# S7CAS-PLEIADES-CARTE-MERE_P02_CONNECTORS.net
KiCad netlist of a schematic drawn in Altium Designer
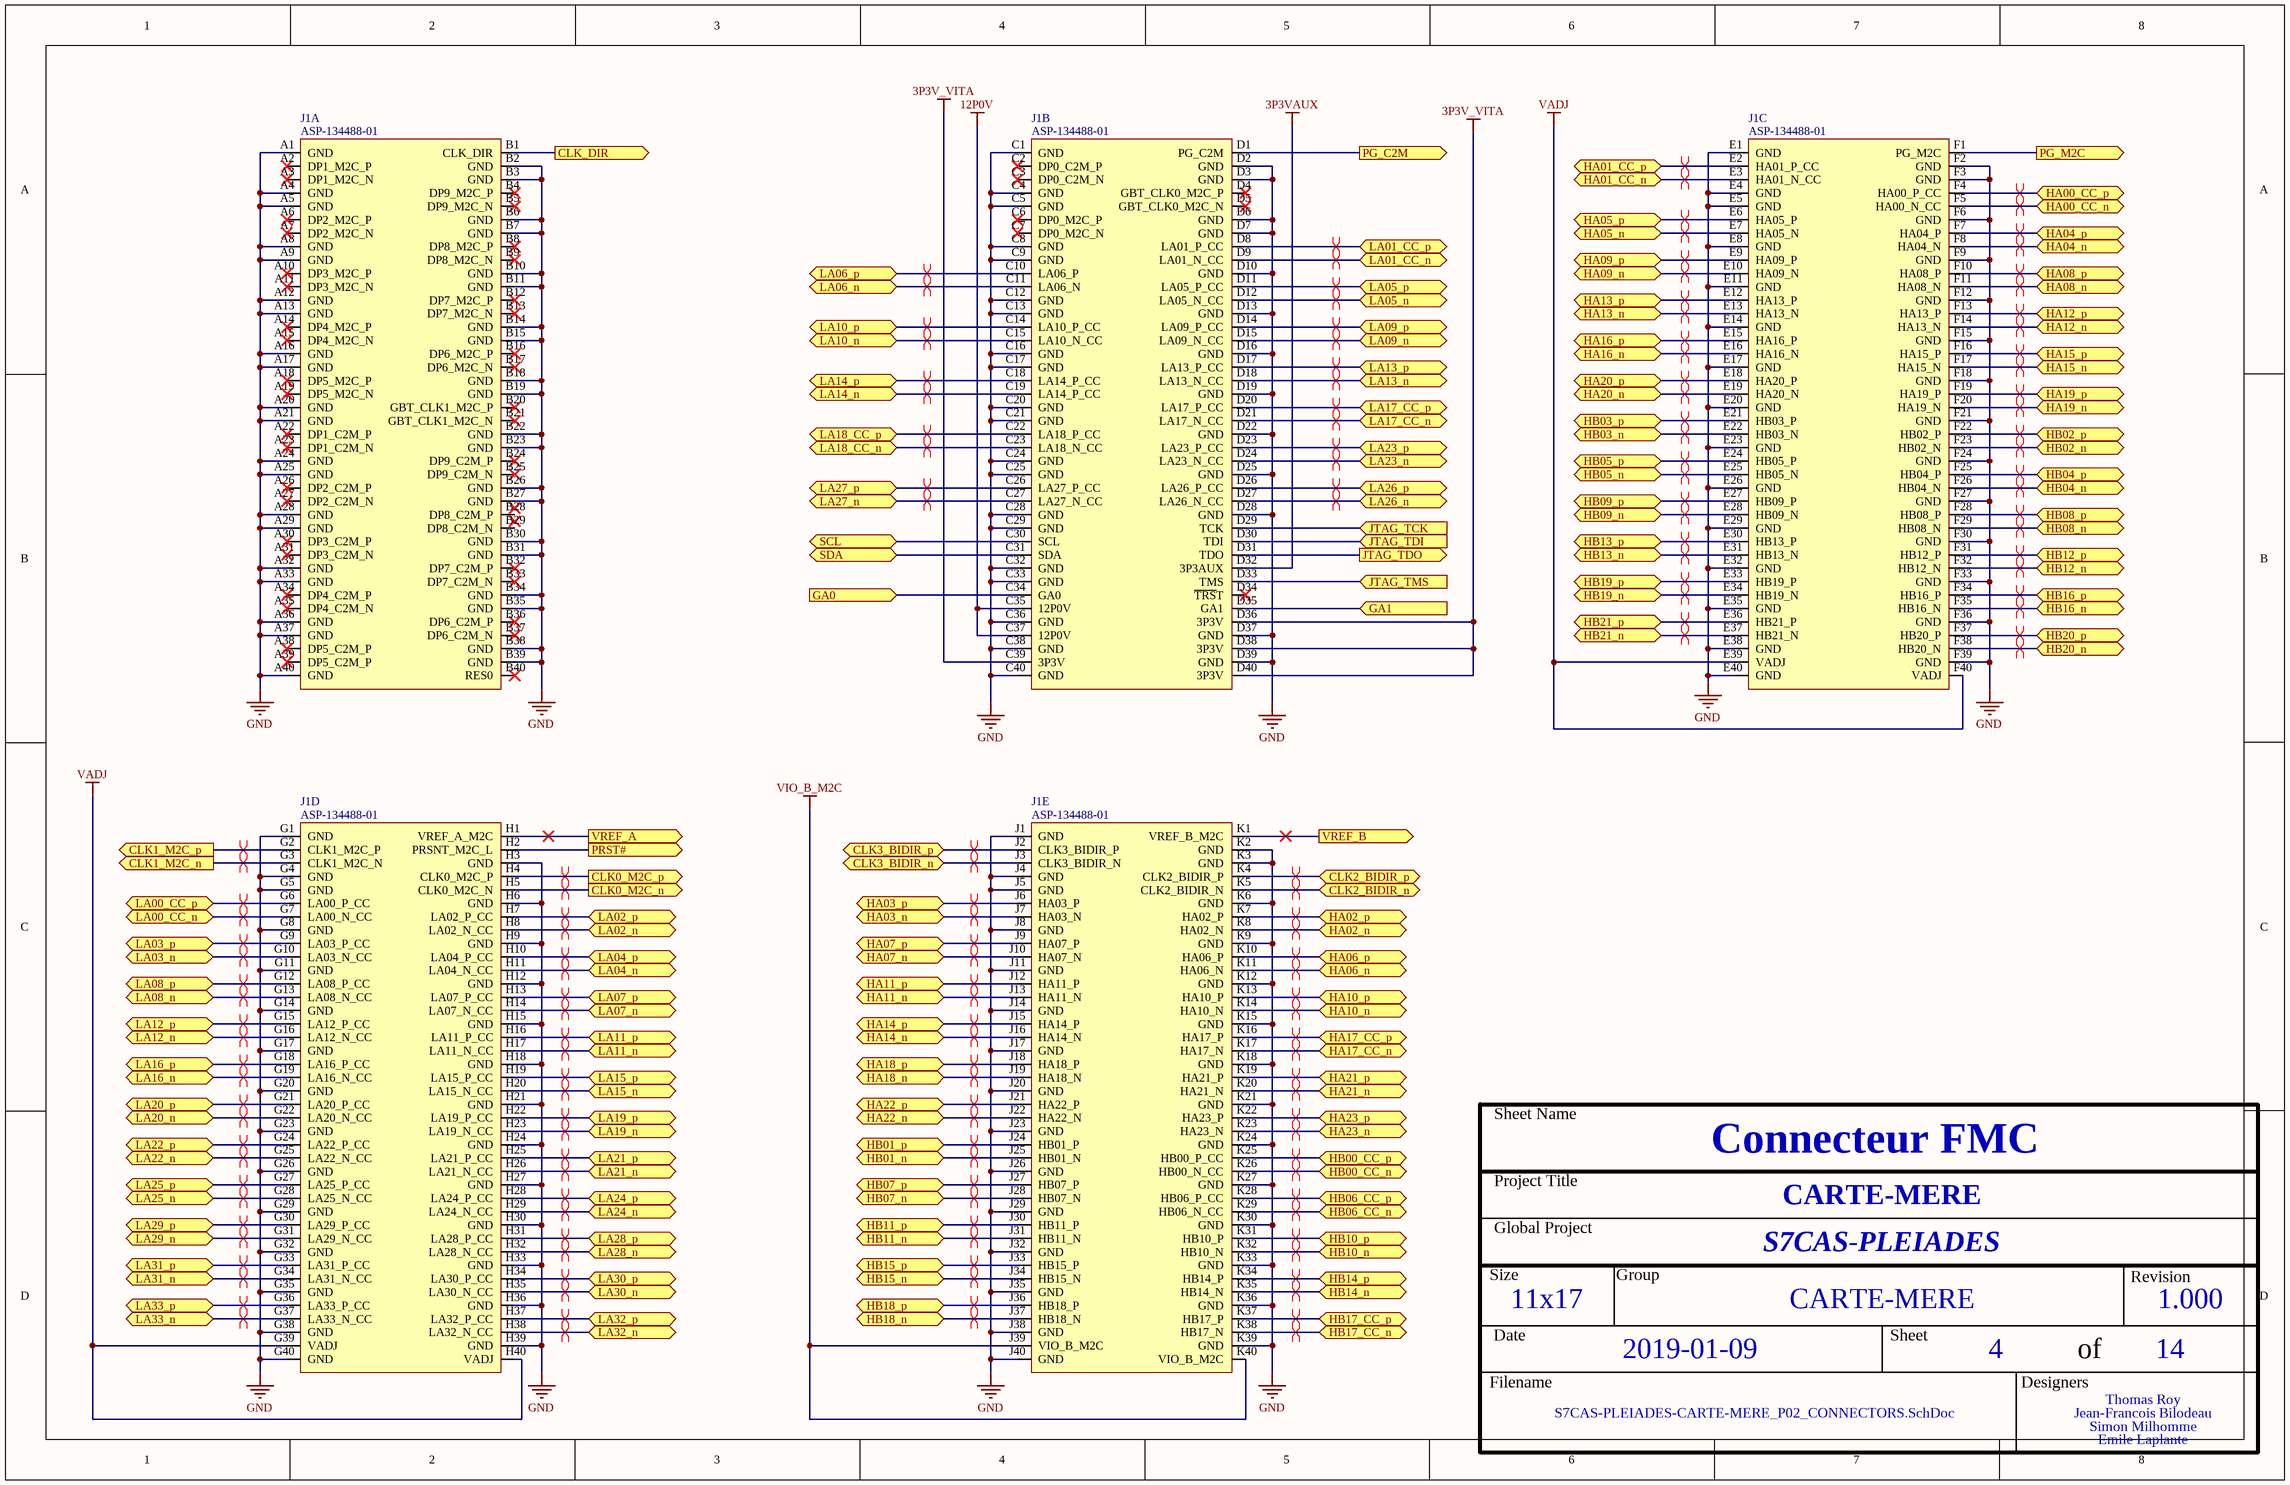
[diagram p0: S7CAS-PLEIADES-CARTE-MERE_P02_CONNECTORS.SchDoc]

(export (version "E")
  (design (tool "Eeschema 10.0.6"))
  (components
    (comp (ref "J1")
      (value "ASP-134488-01")
      (footprint "CONN_SAMTEC_ASP-134488-01")
      (description "CONN - VITA 57 MEZZ MALE (DAUGHTERBOARD) HIGH DENSITY - SMD-400")
      (fields
        (field (name "VOLTAGE") "240VAC")
        (field (name "MFG") "Samtec")
        (field (name "CREATEDBY") "Jonathan Bouchard")
      )
      (libsource (lib "S7CAS_Lib2019_REV1_00") (part "CONN_SAMTEC_ASP-134488-01"))
    )
  )
  (nets
    (net (code "1") (name "/CLK0_M2C_n") (class "Default")
      (node (ref "J1") (pin "H5") (pinfunction "CLK0_M2C_N_H5") (pintype "passive"))
    )
    (net (code "2") (name "/CLK0_M2C_p") (class "Default")
      (node (ref "J1") (pin "H4") (pinfunction "CLK0_M2C_P_H4") (pintype "passive"))
    )
    (net (code "3") (name "/CLK1_M2C_n") (class "Default")
      (node (ref "J1") (pin "G3") (pinfunction "CLK1_M2C_N_G3") (pintype "passive"))
    )
    (net (code "4") (name "/CLK1_M2C_p") (class "Default")
      (node (ref "J1") (pin "G2") (pinfunction "CLK1_M2C_P_G2") (pintype "passive"))
    )
    (net (code "5") (name "/CLK2_BIDIR_n") (class "Default")
      (node (ref "J1") (pin "K5") (pinfunction "CLK2_BIDIR_N_K5") (pintype "passive"))
    )
    (net (code "6") (name "/CLK2_BIDIR_p") (class "Default")
      (node (ref "J1") (pin "K4") (pinfunction "CLK2_BIDIR_P_K4") (pintype "passive"))
    )
    (net (code "7") (name "/CLK3_BIDIR_n") (class "Default")
      (node (ref "J1") (pin "J3") (pinfunction "CLK3_BIDIR_N_J3") (pintype "passive"))
    )
    (net (code "8") (name "/CLK3_BIDIR_p") (class "Default")
      (node (ref "J1") (pin "J2") (pinfunction "CLK3_BIDIR_P_J2") (pintype "passive"))
    )
    (net (code "9") (name "/CLK_DIR") (class "Default")
      (node (ref "J1") (pin "B1") (pinfunction "CLK_DIR_B1") (pintype "passive"))
    )
    (net (code "10") (name "/GA0") (class "Default")
      (node (ref "J1") (pin "C34") (pinfunction "GA0_C34") (pintype "passive"))
    )
    (net (code "11") (name "/GA1") (class "Default")
      (node (ref "J1") (pin "D35") (pinfunction "GA1_D35") (pintype "passive"))
    )
    (net (code "12") (name "/HA00_CC_n") (class "Default")
      (node (ref "J1") (pin "F5") (pinfunction "HA00_N_CC_F5") (pintype "passive"))
    )
    (net (code "13") (name "/HA00_CC_p") (class "Default")
      (node (ref "J1") (pin "F4") (pinfunction "HA00_P_CC_F4") (pintype "passive"))
    )
    (net (code "14") (name "/HA01_CC_n") (class "Default")
      (node (ref "J1") (pin "E3") (pinfunction "HA01_N_CC_E3") (pintype "passive"))
    )
    (net (code "15") (name "/HA01_CC_p") (class "Default")
      (node (ref "J1") (pin "E2") (pinfunction "HA01_P_CC_E2") (pintype "passive"))
    )
    (net (code "16") (name "/HA02_n") (class "Default")
      (node (ref "J1") (pin "K8") (pinfunction "HA02_N_K8") (pintype "passive"))
    )
    (net (code "17") (name "/HA02_p") (class "Default")
      (node (ref "J1") (pin "K7") (pinfunction "HA02_P_K7") (pintype "passive"))
    )
    (net (code "18") (name "/HA03_n") (class "Default")
      (node (ref "J1") (pin "J7") (pinfunction "HA03_N_J7") (pintype "passive"))
    )
    (net (code "19") (name "/HA03_p") (class "Default")
      (node (ref "J1") (pin "J6") (pinfunction "HA03_P_J6") (pintype "passive"))
    )
    (net (code "20") (name "/HA04_n") (class "Default")
      (node (ref "J1") (pin "F8") (pinfunction "HA04_N_F8") (pintype "passive"))
    )
    (net (code "21") (name "/HA04_p") (class "Default")
      (node (ref "J1") (pin "F7") (pinfunction "HA04_P_F7") (pintype "passive"))
    )
    (net (code "22") (name "/HA05_n") (class "Default")
      (node (ref "J1") (pin "E7") (pinfunction "HA05_N_E7") (pintype "passive"))
    )
    (net (code "23") (name "/HA05_p") (class "Default")
      (node (ref "J1") (pin "E6") (pinfunction "HA05_P_E6") (pintype "passive"))
    )
    (net (code "24") (name "/HA06_n") (class "Default")
      (node (ref "J1") (pin "K11") (pinfunction "HA06_N_K11") (pintype "passive"))
    )
    (net (code "25") (name "/HA06_p") (class "Default")
      (node (ref "J1") (pin "K10") (pinfunction "HA06_P_K10") (pintype "passive"))
    )
    (net (code "26") (name "/HA07_n") (class "Default")
      (node (ref "J1") (pin "J10") (pinfunction "HA07_N_J10") (pintype "passive"))
    )
    (net (code "27") (name "/HA07_p") (class "Default")
      (node (ref "J1") (pin "J9") (pinfunction "HA07_P_J9") (pintype "passive"))
    )
    (net (code "28") (name "/HA08_n") (class "Default")
      (node (ref "J1") (pin "F11") (pinfunction "HA08_N_F11") (pintype "passive"))
    )
    (net (code "29") (name "/HA08_p") (class "Default")
      (node (ref "J1") (pin "F10") (pinfunction "HA08_P_F10") (pintype "passive"))
    )
    (net (code "30") (name "/HA09_n") (class "Default")
      (node (ref "J1") (pin "E10") (pinfunction "HA09_N_E10") (pintype "passive"))
    )
    (net (code "31") (name "/HA09_p") (class "Default")
      (node (ref "J1") (pin "E9") (pinfunction "HA09_P_E9") (pintype "passive"))
    )
    (net (code "32") (name "/HA10_n") (class "Default")
      (node (ref "J1") (pin "K14") (pinfunction "HA10_N_K14") (pintype "passive"))
    )
    (net (code "33") (name "/HA10_p") (class "Default")
      (node (ref "J1") (pin "K13") (pinfunction "HA10_P_K13") (pintype "passive"))
    )
    (net (code "34") (name "/HA11_n") (class "Default")
      (node (ref "J1") (pin "J13") (pinfunction "HA11_N_J13") (pintype "passive"))
    )
    (net (code "35") (name "/HA11_p") (class "Default")
      (node (ref "J1") (pin "J12") (pinfunction "HA11_P_J12") (pintype "passive"))
    )
    (net (code "36") (name "/HA12_n") (class "Default")
      (node (ref "J1") (pin "F14") (pinfunction "HA13_N_F14") (pintype "passive"))
    )
    (net (code "37") (name "/HA12_p") (class "Default")
      (node (ref "J1") (pin "F13") (pinfunction "HA13_P_F13") (pintype "passive"))
    )
    (net (code "38") (name "/HA13_n") (class "Default")
      (node (ref "J1") (pin "E13") (pinfunction "HA13_N_E13") (pintype "passive"))
    )
    (net (code "39") (name "/HA13_p") (class "Default")
      (node (ref "J1") (pin "E12") (pinfunction "HA13_P_E12") (pintype "passive"))
    )
    (net (code "40") (name "/HA14_n") (class "Default")
      (node (ref "J1") (pin "J16") (pinfunction "HA14_N_J16") (pintype "passive"))
    )
    (net (code "41") (name "/HA14_p") (class "Default")
      (node (ref "J1") (pin "J15") (pinfunction "HA14_P_J15") (pintype "passive"))
    )
    (net (code "42") (name "/HA15_n") (class "Default")
      (node (ref "J1") (pin "F17") (pinfunction "HA15_N_F17") (pintype "passive"))
    )
    (net (code "43") (name "/HA15_p") (class "Default")
      (node (ref "J1") (pin "F16") (pinfunction "HA15_P_F16") (pintype "passive"))
    )
    (net (code "44") (name "/HA16_n") (class "Default")
      (node (ref "J1") (pin "E16") (pinfunction "HA16_N_E16") (pintype "passive"))
    )
    (net (code "45") (name "/HA16_p") (class "Default")
      (node (ref "J1") (pin "E15") (pinfunction "HA16_P_E15") (pintype "passive"))
    )
    (net (code "46") (name "/HA17_CC_n") (class "Default")
      (node (ref "J1") (pin "K17") (pinfunction "HA17_N_K17") (pintype "passive"))
    )
    (net (code "47") (name "/HA17_CC_p") (class "Default")
      (node (ref "J1") (pin "K16") (pinfunction "HA17_P_K16") (pintype "passive"))
    )
    (net (code "48") (name "/HA18_n") (class "Default")
      (node (ref "J1") (pin "J19") (pinfunction "HA18_N_J19") (pintype "passive"))
    )
    (net (code "49") (name "/HA18_p") (class "Default")
      (node (ref "J1") (pin "J18") (pinfunction "HA18_P_J18") (pintype "passive"))
    )
    (net (code "50") (name "/HA19_n") (class "Default")
      (node (ref "J1") (pin "F20") (pinfunction "HA19_N_F20") (pintype "passive"))
    )
    (net (code "51") (name "/HA19_p") (class "Default")
      (node (ref "J1") (pin "F19") (pinfunction "HA19_P_F19") (pintype "passive"))
    )
    (net (code "52") (name "/HA20_n") (class "Default")
      (node (ref "J1") (pin "E19") (pinfunction "HA20_N_E19") (pintype "passive"))
    )
    (net (code "53") (name "/HA20_p") (class "Default")
      (node (ref "J1") (pin "E18") (pinfunction "HA20_P_E18") (pintype "passive"))
    )
    (net (code "54") (name "/HA21_n") (class "Default")
      (node (ref "J1") (pin "K20") (pinfunction "HA21_N_K20") (pintype "passive"))
    )
    (net (code "55") (name "/HA21_p") (class "Default")
      (node (ref "J1") (pin "K19") (pinfunction "HA21_P_K19") (pintype "passive"))
    )
    (net (code "56") (name "/HA22_n") (class "Default")
      (node (ref "J1") (pin "J22") (pinfunction "HA22_N_J22") (pintype "passive"))
    )
    (net (code "57") (name "/HA22_p") (class "Default")
      (node (ref "J1") (pin "J21") (pinfunction "HA22_P_J21") (pintype "passive"))
    )
    (net (code "58") (name "/HA23_n") (class "Default")
      (node (ref "J1") (pin "K23") (pinfunction "HA23_N_K23") (pintype "passive"))
    )
    (net (code "59") (name "/HA23_p") (class "Default")
      (node (ref "J1") (pin "K22") (pinfunction "HA23_P_K22") (pintype "passive"))
    )
    (net (code "60") (name "/HB00_CC_n") (class "Default")
      (node (ref "J1") (pin "K26") (pinfunction "HB00_N_CC_K26") (pintype "passive"))
    )
    (net (code "61") (name "/HB00_CC_p") (class "Default")
      (node (ref "J1") (pin "K25") (pinfunction "HB00_P_CC_K25") (pintype "passive"))
    )
    (net (code "62") (name "/HB01_n") (class "Default")
      (node (ref "J1") (pin "J25") (pinfunction "HB01_N_J25") (pintype "passive"))
    )
    (net (code "63") (name "/HB01_p") (class "Default")
      (node (ref "J1") (pin "J24") (pinfunction "HB01_P_J24") (pintype "passive"))
    )
    (net (code "64") (name "/HB02_n") (class "Default")
      (node (ref "J1") (pin "F23") (pinfunction "HB02_N_F23") (pintype "passive"))
    )
    (net (code "65") (name "/HB02_p") (class "Default")
      (node (ref "J1") (pin "F22") (pinfunction "HB02_P_F22") (pintype "passive"))
    )
    (net (code "66") (name "/HB03_n") (class "Default")
      (node (ref "J1") (pin "E22") (pinfunction "HB03_N_E22") (pintype "passive"))
    )
    (net (code "67") (name "/HB03_p") (class "Default")
      (node (ref "J1") (pin "E21") (pinfunction "HB03_P_E21") (pintype "passive"))
    )
    (net (code "68") (name "/HB04_n") (class "Default")
      (node (ref "J1") (pin "F26") (pinfunction "HB04_N_F26") (pintype "passive"))
    )
    (net (code "69") (name "/HB04_p") (class "Default")
      (node (ref "J1") (pin "F25") (pinfunction "HB04_P_F25") (pintype "passive"))
    )
    (net (code "70") (name "/HB05_n") (class "Default")
      (node (ref "J1") (pin "E25") (pinfunction "HB05_N_E25") (pintype "passive"))
    )
    (net (code "71") (name "/HB05_p") (class "Default")
      (node (ref "J1") (pin "E24") (pinfunction "HB05_P_E24") (pintype "passive"))
    )
    (net (code "72") (name "/HB06_CC_n") (class "Default")
      (node (ref "J1") (pin "K29") (pinfunction "HB06_N_CC_K29") (pintype "passive"))
    )
    (net (code "73") (name "/HB06_CC_p") (class "Default")
      (node (ref "J1") (pin "K28") (pinfunction "HB06_P_CC_K28") (pintype "passive"))
    )
    (net (code "74") (name "/HB07_n") (class "Default")
      (node (ref "J1") (pin "J28") (pinfunction "HB07_N_J28") (pintype "passive"))
    )
    (net (code "75") (name "/HB07_p") (class "Default")
      (node (ref "J1") (pin "J27") (pinfunction "HB07_P_J27") (pintype "passive"))
    )
    (net (code "76") (name "/HB08_n") (class "Default")
      (node (ref "J1") (pin "F29") (pinfunction "HB08_N_F29") (pintype "passive"))
    )
    (net (code "77") (name "/HB08_p") (class "Default")
      (node (ref "J1") (pin "F28") (pinfunction "HB08_P_F28") (pintype "passive"))
    )
    (net (code "78") (name "/HB09_n") (class "Default")
      (node (ref "J1") (pin "E28") (pinfunction "HB09_N_E28") (pintype "passive"))
    )
    (net (code "79") (name "/HB09_p") (class "Default")
      (node (ref "J1") (pin "E27") (pinfunction "HB09_P_E27") (pintype "passive"))
    )
    (net (code "80") (name "/HB10_n") (class "Default")
      (node (ref "J1") (pin "K32") (pinfunction "HB10_N_K32") (pintype "passive"))
    )
    (net (code "81") (name "/HB10_p") (class "Default")
      (node (ref "J1") (pin "K31") (pinfunction "HB10_P_K31") (pintype "passive"))
    )
    (net (code "82") (name "/HB11_n") (class "Default")
      (node (ref "J1") (pin "J31") (pinfunction "HB11_N_J31") (pintype "passive"))
    )
    (net (code "83") (name "/HB11_p") (class "Default")
      (node (ref "J1") (pin "J30") (pinfunction "HB11_P_J30") (pintype "passive"))
    )
    (net (code "84") (name "/HB12_n") (class "Default")
      (node (ref "J1") (pin "F32") (pinfunction "HB12_N_F32") (pintype "passive"))
    )
    (net (code "85") (name "/HB12_p") (class "Default")
      (node (ref "J1") (pin "F31") (pinfunction "HB12_P_F31") (pintype "passive"))
    )
    (net (code "86") (name "/HB13_n") (class "Default")
      (node (ref "J1") (pin "E31") (pinfunction "HB13_N_E31") (pintype "passive"))
    )
    (net (code "87") (name "/HB13_p") (class "Default")
      (node (ref "J1") (pin "E30") (pinfunction "HB13_P_E30") (pintype "passive"))
    )
    (net (code "88") (name "/HB14_n") (class "Default")
      (node (ref "J1") (pin "K35") (pinfunction "HB14_N_K35") (pintype "passive"))
    )
    (net (code "89") (name "/HB14_p") (class "Default")
      (node (ref "J1") (pin "K34") (pinfunction "HB14_P_K34") (pintype "passive"))
    )
    (net (code "90") (name "/HB15_n") (class "Default")
      (node (ref "J1") (pin "J34") (pinfunction "HB15_N_J34") (pintype "passive"))
    )
    (net (code "91") (name "/HB15_p") (class "Default")
      (node (ref "J1") (pin "J33") (pinfunction "HB15_P_J33") (pintype "passive"))
    )
    (net (code "92") (name "/HB16_n") (class "Default")
      (node (ref "J1") (pin "F35") (pinfunction "HB16_N_F35") (pintype "passive"))
    )
    (net (code "93") (name "/HB16_p") (class "Default")
      (node (ref "J1") (pin "F34") (pinfunction "HB16_P_F34") (pintype "passive"))
    )
    (net (code "94") (name "/HB17_CC_n") (class "Default")
      (node (ref "J1") (pin "K38") (pinfunction "HB17_N_K38") (pintype "passive"))
    )
    (net (code "95") (name "/HB17_CC_p") (class "Default")
      (node (ref "J1") (pin "K37") (pinfunction "HB17_P_K37") (pintype "passive"))
    )
    (net (code "96") (name "/HB18_n") (class "Default")
      (node (ref "J1") (pin "J37") (pinfunction "HB18_N_J37") (pintype "passive"))
    )
    (net (code "97") (name "/HB18_p") (class "Default")
      (node (ref "J1") (pin "J36") (pinfunction "HB18_P_J36") (pintype "passive"))
    )
    (net (code "98") (name "/HB19_n") (class "Default")
      (node (ref "J1") (pin "E34") (pinfunction "HB19_N_E34") (pintype "passive"))
    )
    (net (code "99") (name "/HB19_p") (class "Default")
      (node (ref "J1") (pin "E33") (pinfunction "HB19_P_E33") (pintype "passive"))
    )
    (net (code "100") (name "/HB20_n") (class "Default")
      (node (ref "J1") (pin "F38") (pinfunction "HB20_N_F38") (pintype "passive"))
    )
    (net (code "101") (name "/HB20_p") (class "Default")
      (node (ref "J1") (pin "F37") (pinfunction "HB20_P_F37") (pintype "passive"))
    )
    (net (code "102") (name "/HB21_n") (class "Default")
      (node (ref "J1") (pin "E37") (pinfunction "HB21_N_E37") (pintype "passive"))
    )
    (net (code "103") (name "/HB21_p") (class "Default")
      (node (ref "J1") (pin "E36") (pinfunction "HB21_P_E36") (pintype "passive"))
    )
    (net (code "104") (name "/JTAG_TCK") (class "Default")
      (node (ref "J1") (pin "D29") (pinfunction "TCK_D29") (pintype "passive"))
    )
    (net (code "105") (name "/JTAG_TDI") (class "Default")
      (node (ref "J1") (pin "D30") (pinfunction "TDI_D30") (pintype "passive"))
    )
    (net (code "106") (name "/JTAG_TDO") (class "Default")
      (node (ref "J1") (pin "D31") (pinfunction "TDO_D31") (pintype "passive"))
    )
    (net (code "107") (name "/JTAG_TMS") (class "Default")
      (node (ref "J1") (pin "D33") (pinfunction "TMS_D33") (pintype "passive"))
    )
    (net (code "108") (name "/LA00_CC_n") (class "Default")
      (node (ref "J1") (pin "G7") (pinfunction "LA00_N_CC_G7") (pintype "passive"))
    )
    (net (code "109") (name "/LA00_CC_p") (class "Default")
      (node (ref "J1") (pin "G6") (pinfunction "LA00_P_CC_G6") (pintype "passive"))
    )
    (net (code "110") (name "/LA01_CC_n") (class "Default")
      (node (ref "J1") (pin "D9") (pinfunction "LA01_N_CC_D9") (pintype "passive"))
    )
    (net (code "111") (name "/LA01_CC_p") (class "Default")
      (node (ref "J1") (pin "D8") (pinfunction "LA01_P_CC_D8") (pintype "passive"))
    )
    (net (code "112") (name "/LA02_n") (class "Default")
      (node (ref "J1") (pin "H8") (pinfunction "LA02_N_CC_H8") (pintype "passive"))
    )
    (net (code "113") (name "/LA02_p") (class "Default")
      (node (ref "J1") (pin "H7") (pinfunction "LA02_P_CC_H7") (pintype "passive"))
    )
    (net (code "114") (name "/LA03_n") (class "Default")
      (node (ref "J1") (pin "G10") (pinfunction "LA03_N_CC_G10") (pintype "passive"))
    )
    (net (code "115") (name "/LA03_p") (class "Default")
      (node (ref "J1") (pin "G9") (pinfunction "LA03_P_CC_G9") (pintype "passive"))
    )
    (net (code "116") (name "/LA04_n") (class "Default")
      (node (ref "J1") (pin "H11") (pinfunction "LA04_N_CC_H11") (pintype "passive"))
    )
    (net (code "117") (name "/LA04_p") (class "Default")
      (node (ref "J1") (pin "H10") (pinfunction "LA04_P_CC_H10") (pintype "passive"))
    )
    (net (code "118") (name "/LA05_n") (class "Default")
      (node (ref "J1") (pin "D12") (pinfunction "LA05_N_CC_D12") (pintype "passive"))
    )
    (net (code "119") (name "/LA05_p") (class "Default")
      (node (ref "J1") (pin "D11") (pinfunction "LA05_P_CC_D11") (pintype "passive"))
    )
    (net (code "120") (name "/LA06_n") (class "Default")
      (node (ref "J1") (pin "C11") (pinfunction "LA06_N_CC_C11") (pintype "passive"))
    )
    (net (code "121") (name "/LA06_p") (class "Default")
      (node (ref "J1") (pin "C10") (pinfunction "LA06_P_CC_C10") (pintype "passive"))
    )
    (net (code "122") (name "/LA07_n") (class "Default")
      (node (ref "J1") (pin "H14") (pinfunction "LA07_N_CC_H14") (pintype "passive"))
    )
    (net (code "123") (name "/LA07_p") (class "Default")
      (node (ref "J1") (pin "H13") (pinfunction "LA07_P_CC_H13") (pintype "passive"))
    )
    (net (code "124") (name "/LA08_n") (class "Default")
      (node (ref "J1") (pin "G13") (pinfunction "LA08_N_CC_G13") (pintype "passive"))
    )
    (net (code "125") (name "/LA08_p") (class "Default")
      (node (ref "J1") (pin "G12") (pinfunction "LA08_P_CC_G12") (pintype "passive"))
    )
    (net (code "126") (name "/LA09_n") (class "Default")
      (node (ref "J1") (pin "D15") (pinfunction "LA09_N_CC_D15") (pintype "passive"))
    )
    (net (code "127") (name "/LA09_p") (class "Default")
      (node (ref "J1") (pin "D14") (pinfunction "LA09_P_CC_D14") (pintype "passive"))
    )
    (net (code "128") (name "/LA10_n") (class "Default")
      (node (ref "J1") (pin "C15") (pinfunction "LA10_N_CC_C15") (pintype "passive"))
    )
    (net (code "129") (name "/LA10_p") (class "Default")
      (node (ref "J1") (pin "C14") (pinfunction "LA10_P_CC_C14") (pintype "passive"))
    )
    (net (code "130") (name "/LA11_n") (class "Default")
      (node (ref "J1") (pin "H17") (pinfunction "LA11_N_CC_H17") (pintype "passive"))
    )
    (net (code "131") (name "/LA11_p") (class "Default")
      (node (ref "J1") (pin "H16") (pinfunction "LA11_P_CC_H16") (pintype "passive"))
    )
    (net (code "132") (name "/LA12_n") (class "Default")
      (node (ref "J1") (pin "G16") (pinfunction "LA12_N_CC_G16") (pintype "passive"))
    )
    (net (code "133") (name "/LA12_p") (class "Default")
      (node (ref "J1") (pin "G15") (pinfunction "LA12_P_CC_G15") (pintype "passive"))
    )
    (net (code "134") (name "/LA13_n") (class "Default")
      (node (ref "J1") (pin "D18") (pinfunction "LA13_N_CC_D18") (pintype "passive"))
    )
    (net (code "135") (name "/LA13_p") (class "Default")
      (node (ref "J1") (pin "D17") (pinfunction "LA13_P_CC_D17") (pintype "passive"))
    )
    (net (code "136") (name "/LA14_n") (class "Default")
      (node (ref "J1") (pin "C19") (pinfunction "LA14_P_CC_C19") (pintype "passive"))
    )
    (net (code "137") (name "/LA14_p") (class "Default")
      (node (ref "J1") (pin "C18") (pinfunction "LA14_P_CC_C18") (pintype "passive"))
    )
    (net (code "138") (name "/LA15_n") (class "Default")
      (node (ref "J1") (pin "H20") (pinfunction "LA15_N_CC_H20") (pintype "passive"))
    )
    (net (code "139") (name "/LA15_p") (class "Default")
      (node (ref "J1") (pin "H19") (pinfunction "LA15_P_CC_H19") (pintype "passive"))
    )
    (net (code "140") (name "/LA16_n") (class "Default")
      (node (ref "J1") (pin "G19") (pinfunction "LA16_N_CC_G19") (pintype "passive"))
    )
    (net (code "141") (name "/LA16_p") (class "Default")
      (node (ref "J1") (pin "G18") (pinfunction "LA16_P_CC_G18") (pintype "passive"))
    )
    (net (code "142") (name "/LA17_CC_n") (class "Default")
      (node (ref "J1") (pin "D21") (pinfunction "LA17_N_CC_D21") (pintype "passive"))
    )
    (net (code "143") (name "/LA17_CC_p") (class "Default")
      (node (ref "J1") (pin "D20") (pinfunction "LA17_P_CC_D20") (pintype "passive"))
    )
    (net (code "144") (name "/LA18_CC_n") (class "Default")
      (node (ref "J1") (pin "C23") (pinfunction "LA18_N_CC_C23") (pintype "passive"))
    )
    (net (code "145") (name "/LA18_CC_p") (class "Default")
      (node (ref "J1") (pin "C22") (pinfunction "LA18_P_CC_C22") (pintype "passive"))
    )
    (net (code "146") (name "/LA19_n") (class "Default")
      (node (ref "J1") (pin "H23") (pinfunction "LA19_N_CC_H23") (pintype "passive"))
    )
    (net (code "147") (name "/LA19_p") (class "Default")
      (node (ref "J1") (pin "H22") (pinfunction "LA19_P_CC_H22") (pintype "passive"))
    )
    (net (code "148") (name "/LA20_n") (class "Default")
      (node (ref "J1") (pin "G22") (pinfunction "LA20_N_CC_G22") (pintype "passive"))
    )
    (net (code "149") (name "/LA20_p") (class "Default")
      (node (ref "J1") (pin "G21") (pinfunction "LA20_P_CC_G21") (pintype "passive"))
    )
    (net (code "150") (name "/LA21_n") (class "Default")
      (node (ref "J1") (pin "H26") (pinfunction "LA21_N_CC_H26") (pintype "passive"))
    )
    (net (code "151") (name "/LA21_p") (class "Default")
      (node (ref "J1") (pin "H25") (pinfunction "LA21_P_CC_H25") (pintype "passive"))
    )
    (net (code "152") (name "/LA22_n") (class "Default")
      (node (ref "J1") (pin "G25") (pinfunction "LA22_N_CC_G25") (pintype "passive"))
    )
    (net (code "153") (name "/LA22_p") (class "Default")
      (node (ref "J1") (pin "G24") (pinfunction "LA22_P_CC_G24") (pintype "passive"))
    )
    (net (code "154") (name "/LA23_n") (class "Default")
      (node (ref "J1") (pin "D24") (pinfunction "LA23_N_CC_D24") (pintype "passive"))
    )
    (net (code "155") (name "/LA23_p") (class "Default")
      (node (ref "J1") (pin "D23") (pinfunction "LA23_P_CC_D23") (pintype "passive"))
    )
    (net (code "156") (name "/LA24_n") (class "Default")
      (node (ref "J1") (pin "H29") (pinfunction "LA24_N_CC_H29") (pintype "passive"))
    )
    (net (code "157") (name "/LA24_p") (class "Default")
      (node (ref "J1") (pin "H28") (pinfunction "LA24_P_CC_H28") (pintype "passive"))
    )
    (net (code "158") (name "/LA25_n") (class "Default")
      (node (ref "J1") (pin "G28") (pinfunction "LA25_N_CC_G28") (pintype "passive"))
    )
    (net (code "159") (name "/LA25_p") (class "Default")
      (node (ref "J1") (pin "G27") (pinfunction "LA25_P_CC_G27") (pintype "passive"))
    )
    (net (code "160") (name "/LA26_n") (class "Default")
      (node (ref "J1") (pin "D27") (pinfunction "LA26_N_CC_D27") (pintype "passive"))
    )
    (net (code "161") (name "/LA26_p") (class "Default")
      (node (ref "J1") (pin "D26") (pinfunction "LA26_P_CC_D26") (pintype "passive"))
    )
    (net (code "162") (name "/LA27_n") (class "Default")
      (node (ref "J1") (pin "C27") (pinfunction "LA27_N_CC_C27") (pintype "passive"))
    )
    (net (code "163") (name "/LA27_p") (class "Default")
      (node (ref "J1") (pin "C26") (pinfunction "LA27_P_CC_C26") (pintype "passive"))
    )
    (net (code "164") (name "/LA28_n") (class "Default")
      (node (ref "J1") (pin "H32") (pinfunction "LA28_N_CC_H32") (pintype "passive"))
    )
    (net (code "165") (name "/LA28_p") (class "Default")
      (node (ref "J1") (pin "H31") (pinfunction "LA28_P_CC_H31") (pintype "passive"))
    )
    (net (code "166") (name "/LA29_n") (class "Default")
      (node (ref "J1") (pin "G31") (pinfunction "LA29_N_CC_G31") (pintype "passive"))
    )
    (net (code "167") (name "/LA29_p") (class "Default")
      (node (ref "J1") (pin "G30") (pinfunction "LA29_P_CC_G30") (pintype "passive"))
    )
    (net (code "168") (name "/LA30_n") (class "Default")
      (node (ref "J1") (pin "H35") (pinfunction "LA30_N_CC_H35") (pintype "passive"))
    )
    (net (code "169") (name "/LA30_p") (class "Default")
      (node (ref "J1") (pin "H34") (pinfunction "LA30_P_CC_H34") (pintype "passive"))
    )
    (net (code "170") (name "/LA31_n") (class "Default")
      (node (ref "J1") (pin "G34") (pinfunction "LA31_N_CC_G34") (pintype "passive"))
    )
    (net (code "171") (name "/LA31_p") (class "Default")
      (node (ref "J1") (pin "G33") (pinfunction "LA31_P_CC_G33") (pintype "passive"))
    )
    (net (code "172") (name "/LA32_n") (class "Default")
      (node (ref "J1") (pin "H38") (pinfunction "LA32_N_CC_H38") (pintype "passive"))
    )
    (net (code "173") (name "/LA32_p") (class "Default")
      (node (ref "J1") (pin "H37") (pinfunction "LA32_P_CC_H37") (pintype "passive"))
    )
    (net (code "174") (name "/LA33_n") (class "Default")
      (node (ref "J1") (pin "G37") (pinfunction "LA33_N_CC_G37") (pintype "passive"))
    )
    (net (code "175") (name "/LA33_p") (class "Default")
      (node (ref "J1") (pin "G36") (pinfunction "LA33_P_CC_G36") (pintype "passive"))
    )
    (net (code "176") (name "/PG_C2M") (class "Default")
      (node (ref "J1") (pin "D1") (pinfunction "PG_M2C_D1") (pintype "passive"))
    )
    (net (code "177") (name "/PG_M2C") (class "Default")
      (node (ref "J1") (pin "F1") (pinfunction "PG_M2C_F1") (pintype "passive"))
    )
    (net (code "178") (name "/PRST#") (class "Default")
      (node (ref "J1") (pin "H2") (pinfunction "PRSNT_M2C_L_H2") (pintype "passive"))
    )
    (net (code "179") (name "/SCL") (class "Default")
      (node (ref "J1") (pin "C30") (pinfunction "SCL_C30") (pintype "passive"))
    )
    (net (code "180") (name "/SDA") (class "Default")
      (node (ref "J1") (pin "C31") (pinfunction "SDA_C31") (pintype "passive"))
    )
    (net (code "181") (name "/VREF_A") (class "Default")
      (node (ref "J1") (pin "H1") (pinfunction "VREF_A_M2C_H1") (pintype "passive"))
    )
    (net (code "182") (name "/VREF_B") (class "Default")
      (node (ref "J1") (pin "K1") (pinfunction "VREF_B_M2C_K1") (pintype "passive"))
    )
    (net (code "183") (name "3P3VAUX") (class "Default")
      (node (ref "J1") (pin "D32") (pinfunction "3P3AUX_D32") (pintype "passive"))
    )
    (net (code "184") (name "3P3V_VITA") (class "Default")
      (node (ref "J1") (pin "C39") (pinfunction "3P3V_C39") (pintype "passive"))
      (node (ref "J1") (pin "D36") (pinfunction "3P3V_D36") (pintype "passive"))
      (node (ref "J1") (pin "D38") (pinfunction "3P3V_D38") (pintype "passive"))
      (node (ref "J1") (pin "D40") (pinfunction "3P3V_D40") (pintype "passive"))
    )
    (net (code "185") (name "12P0V") (class "Default")
      (node (ref "J1") (pin "C35") (pinfunction "12P0V_C35") (pintype "passive"))
      (node (ref "J1") (pin "C37") (pinfunction "12P0V_C37") (pintype "passive"))
    )
    (net (code "186") (name "GND") (class "Default")
      (node (ref "J1") (pin "A1") (pinfunction "GND_A1") (pintype "passive"))
      (node (ref "J1") (pin "A12") (pinfunction "GND_A12") (pintype "passive"))
      (node (ref "J1") (pin "A13") (pinfunction "GND_A13") (pintype "passive"))
      (node (ref "J1") (pin "A16") (pinfunction "GND_A16") (pintype "passive"))
      (node (ref "J1") (pin "A17") (pinfunction "GND_A17") (pintype "passive"))
      (node (ref "J1") (pin "A20") (pinfunction "GND_A20") (pintype "passive"))
      (node (ref "J1") (pin "A21") (pinfunction "GND_A21") (pintype "passive"))
      (node (ref "J1") (pin "A24") (pinfunction "GND_A24") (pintype "passive"))
      (node (ref "J1") (pin "A25") (pinfunction "GND_A25") (pintype "passive"))
      (node (ref "J1") (pin "A28") (pinfunction "GND_A28") (pintype "passive"))
      (node (ref "J1") (pin "A29") (pinfunction "GND_A29") (pintype "passive"))
      (node (ref "J1") (pin "A32") (pinfunction "GND_A32") (pintype "passive"))
      (node (ref "J1") (pin "A33") (pinfunction "GND_A33") (pintype "passive"))
      (node (ref "J1") (pin "A36") (pinfunction "GND_A36") (pintype "passive"))
      (node (ref "J1") (pin "A37") (pinfunction "GND_A37") (pintype "passive"))
      (node (ref "J1") (pin "A4") (pinfunction "GND_A4") (pintype "passive"))
      (node (ref "J1") (pin "A40") (pinfunction "GND_A40") (pintype "passive"))
      (node (ref "J1") (pin "A5") (pinfunction "GND_A5") (pintype "passive"))
      (node (ref "J1") (pin "A8") (pinfunction "GND_A8") (pintype "passive"))
      (node (ref "J1") (pin "A9") (pinfunction "GND_A9") (pintype "passive"))
      (node (ref "J1") (pin "B10") (pinfunction "GND_B10") (pintype "passive"))
      (node (ref "J1") (pin "B11") (pinfunction "GND_B11") (pintype "passive"))
      (node (ref "J1") (pin "B14") (pinfunction "GND_B14") (pintype "passive"))
      (node (ref "J1") (pin "B15") (pinfunction "GND_B15") (pintype "passive"))
      (node (ref "J1") (pin "B18") (pinfunction "GND_B18") (pintype "passive"))
      (node (ref "J1") (pin "B19") (pinfunction "GND_B19") (pintype "passive"))
      (node (ref "J1") (pin "B2") (pinfunction "GND_B2") (pintype "passive"))
      (node (ref "J1") (pin "B22") (pinfunction "GND_B22") (pintype "passive"))
      (node (ref "J1") (pin "B23") (pinfunction "GND_B23") (pintype "passive"))
      (node (ref "J1") (pin "B26") (pinfunction "GND_B26") (pintype "passive"))
      (node (ref "J1") (pin "B27") (pinfunction "GND_B27") (pintype "passive"))
      (node (ref "J1") (pin "B3") (pinfunction "GND_B3") (pintype "passive"))
      (node (ref "J1") (pin "B30") (pinfunction "GND_B30") (pintype "passive"))
      (node (ref "J1") (pin "B31") (pinfunction "GND_B31") (pintype "passive"))
      (node (ref "J1") (pin "B34") (pinfunction "GND_B34") (pintype "passive"))
      (node (ref "J1") (pin "B35") (pinfunction "GND_B35") (pintype "passive"))
      (node (ref "J1") (pin "B38") (pinfunction "GND_B38") (pintype "passive"))
      (node (ref "J1") (pin "B39") (pinfunction "GND_B39") (pintype "passive"))
      (node (ref "J1") (pin "B6") (pinfunction "GND_B6") (pintype "passive"))
      (node (ref "J1") (pin "B7") (pinfunction "GND_B7") (pintype "passive"))
      (node (ref "J1") (pin "C1") (pinfunction "GND_C1") (pintype "passive"))
      (node (ref "J1") (pin "C12") (pinfunction "GND_C12") (pintype "passive"))
      (node (ref "J1") (pin "C13") (pinfunction "GND_C13") (pintype "passive"))
      (node (ref "J1") (pin "C16") (pinfunction "GND_C16") (pintype "passive"))
      (node (ref "J1") (pin "C17") (pinfunction "GND_C17") (pintype "passive"))
      (node (ref "J1") (pin "C20") (pinfunction "GND_C20") (pintype "passive"))
      (node (ref "J1") (pin "C21") (pinfunction "GND_C21") (pintype "passive"))
      (node (ref "J1") (pin "C24") (pinfunction "GND_C24") (pintype "passive"))
      (node (ref "J1") (pin "C25") (pinfunction "GND_C25") (pintype "passive"))
      (node (ref "J1") (pin "C28") (pinfunction "GND_C28") (pintype "passive"))
      (node (ref "J1") (pin "C29") (pinfunction "GND_C29") (pintype "passive"))
      (node (ref "J1") (pin "C32") (pinfunction "GND_C32") (pintype "passive"))
      (node (ref "J1") (pin "C33") (pinfunction "GND_C33") (pintype "passive"))
      (node (ref "J1") (pin "C36") (pinfunction "GND_C36") (pintype "passive"))
      (node (ref "J1") (pin "C38") (pinfunction "GND_C38") (pintype "passive"))
      (node (ref "J1") (pin "C4") (pinfunction "GND_C4") (pintype "passive"))
      (node (ref "J1") (pin "C40") (pinfunction "GND_C40") (pintype "passive"))
      (node (ref "J1") (pin "C5") (pinfunction "GND_C5") (pintype "passive"))
      (node (ref "J1") (pin "C8") (pinfunction "GND_C8") (pintype "passive"))
      (node (ref "J1") (pin "C9") (pinfunction "GND_C9") (pintype "passive"))
      (node (ref "J1") (pin "D10") (pinfunction "GND_D10") (pintype "passive"))
      (node (ref "J1") (pin "D13") (pinfunction "GND_D13") (pintype "passive"))
      (node (ref "J1") (pin "D16") (pinfunction "GND_D16") (pintype "passive"))
      (node (ref "J1") (pin "D19") (pinfunction "GND_D19") (pintype "passive"))
      (node (ref "J1") (pin "D2") (pinfunction "GND_D2") (pintype "passive"))
      (node (ref "J1") (pin "D22") (pinfunction "GND_D22") (pintype "passive"))
      (node (ref "J1") (pin "D25") (pinfunction "GND_D25") (pintype "passive"))
      (node (ref "J1") (pin "D28") (pinfunction "GND_D28") (pintype "passive"))
      (node (ref "J1") (pin "D3") (pinfunction "GND_D3") (pintype "passive"))
      (node (ref "J1") (pin "D37") (pinfunction "GND_D37") (pintype "passive"))
      (node (ref "J1") (pin "D39") (pinfunction "GND_D39") (pintype "passive"))
      (node (ref "J1") (pin "D6") (pinfunction "GND_D6") (pintype "passive"))
      (node (ref "J1") (pin "D7") (pinfunction "GND_D7") (pintype "passive"))
      (node (ref "J1") (pin "E1") (pinfunction "GND_E1") (pintype "passive"))
      (node (ref "J1") (pin "E11") (pinfunction "GND_E11") (pintype "passive"))
      (node (ref "J1") (pin "E14") (pinfunction "GND_E14") (pintype "passive"))
      (node (ref "J1") (pin "E17") (pinfunction "GND_E17") (pintype "passive"))
      (node (ref "J1") (pin "E20") (pinfunction "GND_E20") (pintype "passive"))
      (node (ref "J1") (pin "E23") (pinfunction "GND_E23") (pintype "passive"))
      (node (ref "J1") (pin "E26") (pinfunction "GND_E26") (pintype "passive"))
      (node (ref "J1") (pin "E29") (pinfunction "GND_E29") (pintype "passive"))
      (node (ref "J1") (pin "E32") (pinfunction "GND_E32") (pintype "passive"))
      (node (ref "J1") (pin "E35") (pinfunction "GND_E35") (pintype "passive"))
      (node (ref "J1") (pin "E38") (pinfunction "GND_E38") (pintype "passive"))
      (node (ref "J1") (pin "E4") (pinfunction "GND_E4") (pintype "passive"))
      (node (ref "J1") (pin "E40") (pinfunction "GND_E40") (pintype "passive"))
      (node (ref "J1") (pin "E5") (pinfunction "GND_E5") (pintype "passive"))
      (node (ref "J1") (pin "E8") (pinfunction "GND_E8") (pintype "passive"))
      (node (ref "J1") (pin "F12") (pinfunction "GND_F12") (pintype "passive"))
      (node (ref "J1") (pin "F15") (pinfunction "GND_F15") (pintype "passive"))
      (node (ref "J1") (pin "F18") (pinfunction "GND_F18") (pintype "passive"))
      (node (ref "J1") (pin "F2") (pinfunction "GND_F2") (pintype "passive"))
      (node (ref "J1") (pin "F21") (pinfunction "GND_F21") (pintype "passive"))
      (node (ref "J1") (pin "F24") (pinfunction "GND_F24") (pintype "passive"))
      (node (ref "J1") (pin "F27") (pinfunction "GND_F27") (pintype "passive"))
      (node (ref "J1") (pin "F3") (pinfunction "GND_F3") (pintype "passive"))
      (node (ref "J1") (pin "F30") (pinfunction "GND_F30") (pintype "passive"))
      (node (ref "J1") (pin "F33") (pinfunction "GND_F33") (pintype "passive"))
      (node (ref "J1") (pin "F36") (pinfunction "GND_F36") (pintype "passive"))
      (node (ref "J1") (pin "F39") (pinfunction "GND_F39") (pintype "passive"))
      (node (ref "J1") (pin "F6") (pinfunction "GND_F6") (pintype "passive"))
      (node (ref "J1") (pin "F9") (pinfunction "GND_F9") (pintype "passive"))
      (node (ref "J1") (pin "G1") (pinfunction "GND_G1") (pintype "passive"))
      (node (ref "J1") (pin "G11") (pinfunction "GND_G11") (pintype "passive"))
      (node (ref "J1") (pin "G14") (pinfunction "GND_G14") (pintype "passive"))
      (node (ref "J1") (pin "G17") (pinfunction "GND_G17") (pintype "passive"))
      (node (ref "J1") (pin "G20") (pinfunction "GND_G20") (pintype "passive"))
      (node (ref "J1") (pin "G23") (pinfunction "GND_G23") (pintype "passive"))
      (node (ref "J1") (pin "G26") (pinfunction "GND_G26") (pintype "passive"))
      (node (ref "J1") (pin "G29") (pinfunction "GND_G29") (pintype "passive"))
      (node (ref "J1") (pin "G32") (pinfunction "GND_G32") (pintype "passive"))
      (node (ref "J1") (pin "G35") (pinfunction "GND_G35") (pintype "passive"))
      (node (ref "J1") (pin "G38") (pinfunction "GND_G38") (pintype "passive"))
      (node (ref "J1") (pin "G4") (pinfunction "GND_G4") (pintype "passive"))
      (node (ref "J1") (pin "G40") (pinfunction "GND_G40") (pintype "passive"))
      (node (ref "J1") (pin "G5") (pinfunction "GND_G5") (pintype "passive"))
      (node (ref "J1") (pin "G8") (pinfunction "GND_G8") (pintype "passive"))
      (node (ref "J1") (pin "H12") (pinfunction "GND_H12") (pintype "passive"))
      (node (ref "J1") (pin "H15") (pinfunction "GND_H15") (pintype "passive"))
      (node (ref "J1") (pin "H18") (pinfunction "GND_H18") (pintype "passive"))
      (node (ref "J1") (pin "H21") (pinfunction "GND_H21") (pintype "passive"))
      (node (ref "J1") (pin "H24") (pinfunction "GND_H24") (pintype "passive"))
      (node (ref "J1") (pin "H27") (pinfunction "GND_H27") (pintype "passive"))
      (node (ref "J1") (pin "H3") (pinfunction "GND_H3") (pintype "passive"))
      (node (ref "J1") (pin "H30") (pinfunction "GND_H30") (pintype "passive"))
      (node (ref "J1") (pin "H33") (pinfunction "GND_H33") (pintype "passive"))
      (node (ref "J1") (pin "H36") (pinfunction "GND_H36") (pintype "passive"))
      (node (ref "J1") (pin "H39") (pinfunction "GND_H39") (pintype "passive"))
      (node (ref "J1") (pin "H6") (pinfunction "GND_H6") (pintype "passive"))
      (node (ref "J1") (pin "H9") (pinfunction "GND_H9") (pintype "passive"))
      (node (ref "J1") (pin "J1") (pinfunction "GND_J1") (pintype "passive"))
      (node (ref "J1") (pin "J11") (pinfunction "GND_J11") (pintype "passive"))
      (node (ref "J1") (pin "J14") (pinfunction "GND_J14") (pintype "passive"))
      (node (ref "J1") (pin "J17") (pinfunction "GND_J17") (pintype "passive"))
      (node (ref "J1") (pin "J20") (pinfunction "GND_J20") (pintype "passive"))
      (node (ref "J1") (pin "J23") (pinfunction "GND_J23") (pintype "passive"))
      (node (ref "J1") (pin "J26") (pinfunction "GND_J26") (pintype "passive"))
      (node (ref "J1") (pin "J29") (pinfunction "GND_J29") (pintype "passive"))
      (node (ref "J1") (pin "J32") (pinfunction "GND_J32") (pintype "passive"))
      (node (ref "J1") (pin "J35") (pinfunction "GND_J35") (pintype "passive"))
      (node (ref "J1") (pin "J38") (pinfunction "GND_J38") (pintype "passive"))
      (node (ref "J1") (pin "J4") (pinfunction "GND_J4") (pintype "passive"))
      (node (ref "J1") (pin "J40") (pinfunction "GND_J40") (pintype "passive"))
      (node (ref "J1") (pin "J5") (pinfunction "GND_J5") (pintype "passive"))
      (node (ref "J1") (pin "J8") (pinfunction "GND_J8") (pintype "passive"))
      (node (ref "J1") (pin "K12") (pinfunction "GND_K12") (pintype "passive"))
      (node (ref "J1") (pin "K15") (pinfunction "GND_K15") (pintype "passive"))
      (node (ref "J1") (pin "K18") (pinfunction "GND_K18") (pintype "passive"))
      (node (ref "J1") (pin "K2") (pinfunction "GND_K2") (pintype "passive"))
      (node (ref "J1") (pin "K21") (pinfunction "GND_K21") (pintype "passive"))
      (node (ref "J1") (pin "K24") (pinfunction "GND_K24") (pintype "passive"))
      (node (ref "J1") (pin "K27") (pinfunction "GND_K27") (pintype "passive"))
      (node (ref "J1") (pin "K3") (pinfunction "GND_K3") (pintype "passive"))
      (node (ref "J1") (pin "K30") (pinfunction "GND_K30") (pintype "passive"))
      (node (ref "J1") (pin "K33") (pinfunction "GND_K33") (pintype "passive"))
      (node (ref "J1") (pin "K36") (pinfunction "GND_K36") (pintype "passive"))
      (node (ref "J1") (pin "K39") (pinfunction "GND_K39") (pintype "passive"))
      (node (ref "J1") (pin "K6") (pinfunction "GND_K6") (pintype "passive"))
      (node (ref "J1") (pin "K9") (pinfunction "GND_K9") (pintype "passive"))
    )
    (net (code "187") (name "VADJ") (class "Default")
      (node (ref "J1") (pin "E39") (pinfunction "VADJ_E39") (pintype "passive"))
      (node (ref "J1") (pin "F40") (pinfunction "VADJ_F40") (pintype "passive"))
      (node (ref "J1") (pin "G39") (pinfunction "VADJ_G39") (pintype "passive"))
      (node (ref "J1") (pin "H40") (pinfunction "VADJ_H40") (pintype "passive"))
    )
    (net (code "188") (name "VIO_B_M2C") (class "Default")
      (node (ref "J1") (pin "J39") (pinfunction "VIO_B_M2C_J39") (pintype "passive"))
      (node (ref "J1") (pin "K40") (pinfunction "VIO_B_M2C_K40") (pintype "passive"))
    )
    (net (code "189") (name "unconnected-(J1A-DP1_C2M_N-PadA23)") (class "Default")
      (node (ref "J1") (pin "A23") (pinfunction "DP1_C2M_N_A23") (pintype "passive+no_connect"))
    )
    (net (code "190") (name "unconnected-(J1A-DP1_C2M_P-PadA22)") (class "Default")
      (node (ref "J1") (pin "A22") (pinfunction "DP1_C2M_P_A22") (pintype "passive+no_connect"))
    )
    (net (code "191") (name "unconnected-(J1A-DP1_M2C_N-PadA3)") (class "Default")
      (node (ref "J1") (pin "A3") (pinfunction "DP1_M2C_N_A3") (pintype "passive+no_connect"))
    )
    (net (code "192") (name "unconnected-(J1A-DP1_M2C_P-PadA2)") (class "Default")
      (node (ref "J1") (pin "A2") (pinfunction "DP1_M2C_P_A2") (pintype "passive+no_connect"))
    )
    (net (code "193") (name "unconnected-(J1A-DP2_C2M_N-PadA27)") (class "Default")
      (node (ref "J1") (pin "A27") (pinfunction "DP2_C2M_N_A27") (pintype "passive+no_connect"))
    )
    (net (code "194") (name "unconnected-(J1A-DP2_C2M_P-PadA26)") (class "Default")
      (node (ref "J1") (pin "A26") (pinfunction "DP2_C2M_P_A26") (pintype "passive+no_connect"))
    )
    (net (code "195") (name "unconnected-(J1A-DP2_M2C_N-PadA7)") (class "Default")
      (node (ref "J1") (pin "A7") (pinfunction "DP2_M2C_N_A7") (pintype "passive+no_connect"))
    )
    (net (code "196") (name "unconnected-(J1A-DP2_M2C_P-PadA6)") (class "Default")
      (node (ref "J1") (pin "A6") (pinfunction "DP2_M2C_P_A6") (pintype "passive+no_connect"))
    )
    (net (code "197") (name "unconnected-(J1A-DP3_C2M_N-PadA31)") (class "Default")
      (node (ref "J1") (pin "A31") (pinfunction "DP3_C2M_N_A31") (pintype "passive+no_connect"))
    )
    (net (code "198") (name "unconnected-(J1A-DP3_C2M_P-PadA30)") (class "Default")
      (node (ref "J1") (pin "A30") (pinfunction "DP3_C2M_P_A30") (pintype "passive+no_connect"))
    )
    (net (code "199") (name "unconnected-(J1A-DP3_M2C_N-PadA11)") (class "Default")
      (node (ref "J1") (pin "A11") (pinfunction "DP3_M2C_N_A11") (pintype "passive+no_connect"))
    )
    (net (code "200") (name "unconnected-(J1A-DP3_M2C_P-PadA10)") (class "Default")
      (node (ref "J1") (pin "A10") (pinfunction "DP3_M2C_P_A10") (pintype "passive+no_connect"))
    )
    (net (code "201") (name "unconnected-(J1A-DP4_C2M_N-PadA35)") (class "Default")
      (node (ref "J1") (pin "A35") (pinfunction "DP4_C2M_N_A35") (pintype "passive+no_connect"))
    )
    (net (code "202") (name "unconnected-(J1A-DP4_C2M_P-PadA34)") (class "Default")
      (node (ref "J1") (pin "A34") (pinfunction "DP4_C2M_P_A34") (pintype "passive+no_connect"))
    )
    (net (code "203") (name "unconnected-(J1A-DP4_M2C_N-PadA15)") (class "Default")
      (node (ref "J1") (pin "A15") (pinfunction "DP4_M2C_N_A15") (pintype "passive+no_connect"))
    )
    (net (code "204") (name "unconnected-(J1A-DP4_M2C_P-PadA14)") (class "Default")
      (node (ref "J1") (pin "A14") (pinfunction "DP4_M2C_P_A14") (pintype "passive+no_connect"))
    )
    (net (code "205") (name "unconnected-(J1A-DP5_C2M_P-PadA38)") (class "Default")
      (node (ref "J1") (pin "A38") (pinfunction "DP5_C2M_P_A38") (pintype "passive+no_connect"))
    )
    (net (code "206") (name "unconnected-(J1A-DP5_C2M_P-PadA39)") (class "Default")
      (node (ref "J1") (pin "A39") (pinfunction "DP5_C2M_P_A39") (pintype "passive+no_connect"))
    )
    (net (code "207") (name "unconnected-(J1A-DP5_M2C_N-PadA19)") (class "Default")
      (node (ref "J1") (pin "A19") (pinfunction "DP5_M2C_N_A19") (pintype "passive+no_connect"))
    )
    (net (code "208") (name "unconnected-(J1A-DP5_M2C_P-PadA18)") (class "Default")
      (node (ref "J1") (pin "A18") (pinfunction "DP5_M2C_P_A18") (pintype "passive+no_connect"))
    )
    (net (code "209") (name "unconnected-(J1A-DP6_C2M_N-PadB37)") (class "Default")
      (node (ref "J1") (pin "B37") (pinfunction "DP6_C2M_N_B37") (pintype "passive+no_connect"))
    )
    (net (code "210") (name "unconnected-(J1A-DP6_C2M_P-PadB36)") (class "Default")
      (node (ref "J1") (pin "B36") (pinfunction "DP6_C2M_P_B36") (pintype "passive+no_connect"))
    )
    (net (code "211") (name "unconnected-(J1A-DP6_M2C_N-PadB17)") (class "Default")
      (node (ref "J1") (pin "B17") (pinfunction "DP6_M2C_N_B17") (pintype "passive+no_connect"))
    )
    (net (code "212") (name "unconnected-(J1A-DP6_M2C_P-PadB16)") (class "Default")
      (node (ref "J1") (pin "B16") (pinfunction "DP6_M2C_P_B16") (pintype "passive+no_connect"))
    )
    (net (code "213") (name "unconnected-(J1A-DP7_C2M_N-PadB33)") (class "Default")
      (node (ref "J1") (pin "B33") (pinfunction "DP7_C2M_N_B33") (pintype "passive+no_connect"))
    )
    (net (code "214") (name "unconnected-(J1A-DP7_C2M_P-PadB32)") (class "Default")
      (node (ref "J1") (pin "B32") (pinfunction "DP7_C2M_P_B32") (pintype "passive+no_connect"))
    )
    (net (code "215") (name "unconnected-(J1A-DP7_M2C_N-PadB13)") (class "Default")
      (node (ref "J1") (pin "B13") (pinfunction "DP7_M2C_N_B13") (pintype "passive+no_connect"))
    )
    (net (code "216") (name "unconnected-(J1A-DP7_M2C_P-PadB12)") (class "Default")
      (node (ref "J1") (pin "B12") (pinfunction "DP7_M2C_P_B12") (pintype "passive+no_connect"))
    )
    (net (code "217") (name "unconnected-(J1A-DP8_C2M_N-PadB29)") (class "Default")
      (node (ref "J1") (pin "B29") (pinfunction "DP8_C2M_N_B29") (pintype "passive"))
    )
    (net (code "218") (name "unconnected-(J1A-DP8_C2M_P-PadB28)") (class "Default")
      (node (ref "J1") (pin "B28") (pinfunction "DP8_C2M_P_B28") (pintype "passive"))
    )
    (net (code "219") (name "unconnected-(J1A-DP8_M2C_N-PadB9)") (class "Default")
      (node (ref "J1") (pin "B9") (pinfunction "DP8_M2C_N_B9") (pintype "passive+no_connect"))
    )
    (net (code "220") (name "unconnected-(J1A-DP8_M2C_P-PadB8)") (class "Default")
      (node (ref "J1") (pin "B8") (pinfunction "DP8_M2C_P_B8") (pintype "passive+no_connect"))
    )
    (net (code "221") (name "unconnected-(J1A-DP9_C2M_N-PadB25)") (class "Default")
      (node (ref "J1") (pin "B25") (pinfunction "DP9_C2M_N_B25") (pintype "passive+no_connect"))
    )
    (net (code "222") (name "unconnected-(J1A-DP9_C2M_P-PadB24)") (class "Default")
      (node (ref "J1") (pin "B24") (pinfunction "DP9_C2M_P_B24") (pintype "passive+no_connect"))
    )
    (net (code "223") (name "unconnected-(J1A-DP9_M2C_N-PadB5)") (class "Default")
      (node (ref "J1") (pin "B5") (pinfunction "DP9_M2C_N_B5") (pintype "passive+no_connect"))
    )
    (net (code "224") (name "unconnected-(J1A-DP9_M2C_P-PadB4)") (class "Default")
      (node (ref "J1") (pin "B4") (pinfunction "DP9_M2C_P_B4") (pintype "passive+no_connect"))
    )
    (net (code "225") (name "unconnected-(J1A-GBT_CLK1_M2C_N-PadB21)") (class "Default")
      (node (ref "J1") (pin "B21") (pinfunction "GBT_CLK1_M2C_N_B21") (pintype "passive+no_connect"))
    )
    (net (code "226") (name "unconnected-(J1A-GBT_CLK1_M2C_P-PadB20)") (class "Default")
      (node (ref "J1") (pin "B20") (pinfunction "GBT_CLK1_M2C_P_B20") (pintype "passive+no_connect"))
    )
    (net (code "227") (name "unconnected-(J1A-RES0-PadB40)") (class "Default")
      (node (ref "J1") (pin "B40") (pinfunction "RES0_B40") (pintype "passive+no_connect"))
    )
    (net (code "228") (name "unconnected-(J1B-DP0_C2M_N-PadC3)") (class "Default")
      (node (ref "J1") (pin "C3") (pinfunction "DP0_C2M_N_C3") (pintype "passive+no_connect"))
    )
    (net (code "229") (name "unconnected-(J1B-DP0_C2M_P-PadC2)") (class "Default")
      (node (ref "J1") (pin "C2") (pinfunction "DP0_C2M_P_C2") (pintype "passive+no_connect"))
    )
    (net (code "230") (name "unconnected-(J1B-DP0_M2C_N-PadC7)") (class "Default")
      (node (ref "J1") (pin "C7") (pinfunction "DP0_M2C_N_C7") (pintype "passive+no_connect"))
    )
    (net (code "231") (name "unconnected-(J1B-DP0_M2C_P-PadC6)") (class "Default")
      (node (ref "J1") (pin "C6") (pinfunction "DP0_M2C_P_C6") (pintype "passive+no_connect"))
    )
    (net (code "232") (name "unconnected-(J1B-GBT_CLK0_M2C_N-PadD5)") (class "Default")
      (node (ref "J1") (pin "D5") (pinfunction "GBT_CLK0_M2C_N_D5") (pintype "passive+no_connect"))
    )
    (net (code "233") (name "unconnected-(J1B-GBT_CLK0_M2C_P-PadD4)") (class "Default")
      (node (ref "J1") (pin "D4") (pinfunction "GBT_CLK0_M2C_P_D4") (pintype "passive+no_connect"))
    )
    (net (code "234") (name "unconnected-(J1B-~{TRS}T-PadD34)") (class "Default")
      (node (ref "J1") (pin "D34") (pinfunction "~{TRS}T_D34") (pintype "passive+no_connect"))
    )
  )
)
